# sb3.net
KiCad netlist of a schematic drawn in EAGLE
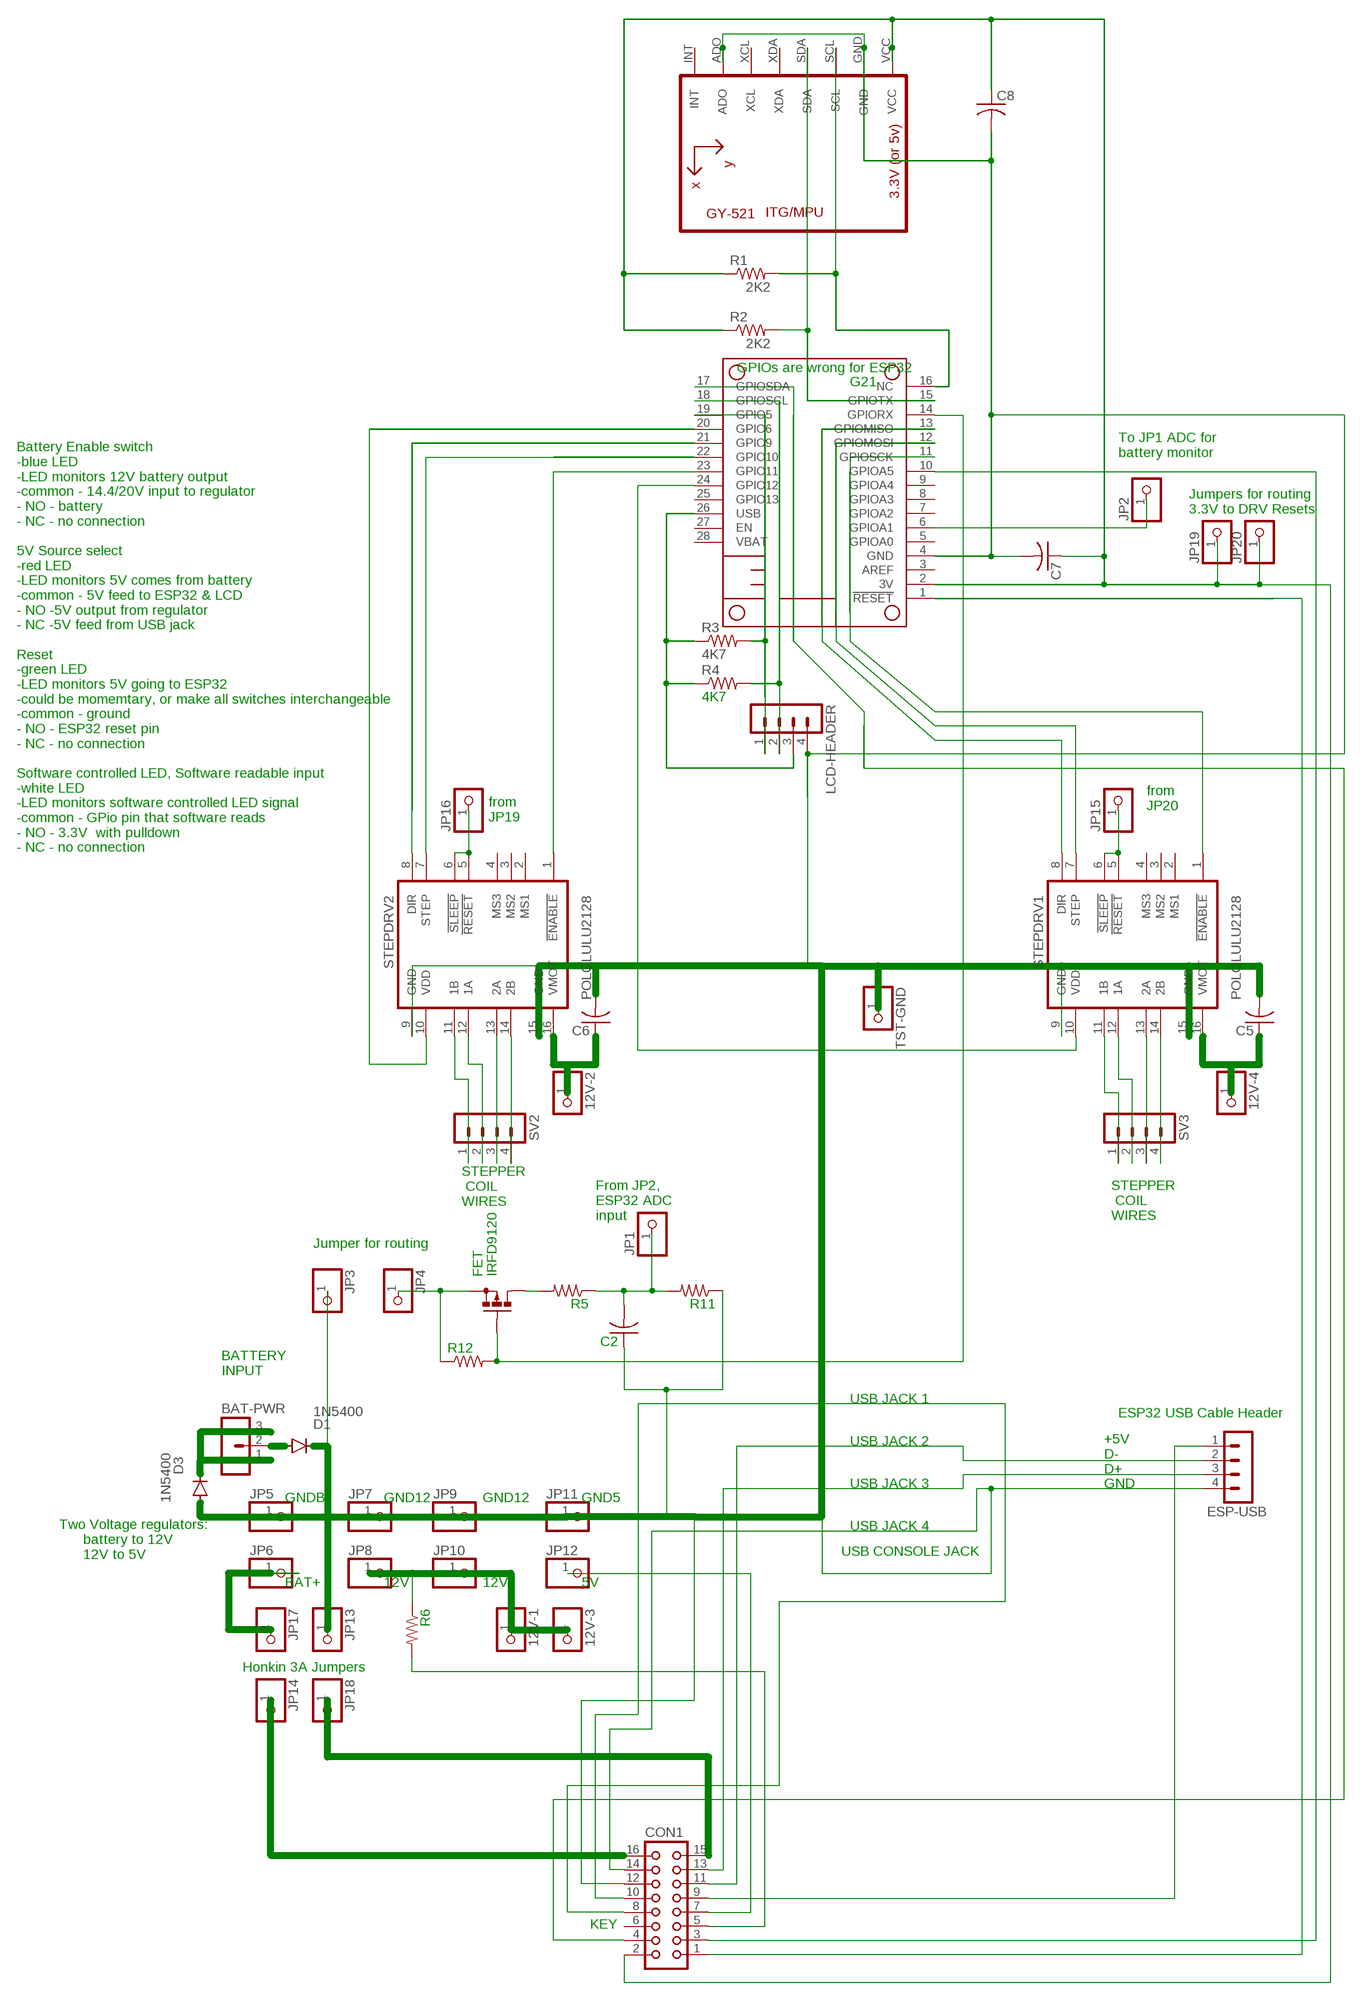
[diagram p0: schematic, sheet 1]

(export (version "E")
  (design (tool "Eeschema 10.0.6"))
  (components
    (comp (ref "12V-1")
      (value "PINHD-1X1")
      (footprint "eagle-import:1X01")
      (libsource (lib "eagle-import") (part "PINHD-1X1"))
    )
    (comp (ref "12V-2")
      (value "PINHD-1X1")
      (footprint "eagle-import:1X01")
      (libsource (lib "eagle-import") (part "PINHD-1X1"))
    )
    (comp (ref "12V-3")
      (value "PINHD-1X1")
      (footprint "eagle-import:1X01")
      (libsource (lib "eagle-import") (part "PINHD-1X1"))
    )
    (comp (ref "12V-4")
      (value "PINHD-1X1")
      (footprint "eagle-import:1X01")
      (libsource (lib "eagle-import") (part "PINHD-1X1"))
    )
    (comp (ref "BAT-PWR")
      (value "MA03-1")
      (footprint "eagle-import:MA03-1")
      (libsource (lib "eagle-import") (part "MA03-1"))
    )
    (comp (ref "C2")
      (value "C-US050-025X075")
      (footprint "eagle-import:C050-025X075")
      (libsource (lib "eagle-import") (part "C-US050-025X075"))
    )
    (comp (ref "C5")
      (value "C-US050-024X044")
      (footprint "eagle-import:C050-024X044")
      (libsource (lib "eagle-import") (part "C-US050-024X044"))
    )
    (comp (ref "C6")
      (value "C-US050-024X044")
      (footprint "eagle-import:C050-024X044")
      (libsource (lib "eagle-import") (part "C-US050-024X044"))
    )
    (comp (ref "C7")
      (value "C-US050-024X044")
      (footprint "eagle-import:C050-024X044")
      (libsource (lib "eagle-import") (part "C-US050-024X044"))
    )
    (comp (ref "C8")
      (value "C-US050-024X044")
      (footprint "eagle-import:C050-024X044")
      (libsource (lib "eagle-import") (part "C-US050-024X044"))
    )
    (comp (ref "CON1")
      (value "CON16")
      (footprint "eagle-import:CON16")
      (libsource (lib "eagle-import") (part "CON16"))
    )
    (comp (ref "D1")
      (value "1N5400")
      (footprint "eagle-import:DO201-15")
      (libsource (lib "eagle-import") (part "1N5400"))
    )
    (comp (ref "D3")
      (value "1N5400")
      (footprint "eagle-import:DO201-15")
      (libsource (lib "eagle-import") (part "1N5400"))
    )
    (comp (ref "ESP-USB")
      (value "MA04-1")
      (footprint "eagle-import:MA04-1")
      (libsource (lib "eagle-import") (part "MA04-1"))
    )
    (comp (ref "FET")
      (value "IRFD9120")
      (footprint "eagle-import:C370-01")
      (libsource (lib "eagle-import") (part "IRFD9120"))
    )
    (comp (ref "JP1")
      (value "PINHD-1X1")
      (footprint "eagle-import:1X01")
      (libsource (lib "eagle-import") (part "PINHD-1X1"))
    )
    (comp (ref "JP2")
      (value "PINHD-1X1")
      (footprint "eagle-import:1X01")
      (libsource (lib "eagle-import") (part "PINHD-1X1"))
    )
    (comp (ref "JP3")
      (value "PINHD-1X1")
      (footprint "eagle-import:1X01")
      (libsource (lib "eagle-import") (part "PINHD-1X1"))
    )
    (comp (ref "JP4")
      (value "PINHD-1X1")
      (footprint "eagle-import:1X01")
      (libsource (lib "eagle-import") (part "PINHD-1X1"))
    )
    (comp (ref "JP5")
      (value "PINHD-1X1")
      (footprint "eagle-import:1X01")
      (libsource (lib "eagle-import") (part "PINHD-1X1"))
    )
    (comp (ref "JP6")
      (value "PINHD-1X1")
      (footprint "eagle-import:1X01")
      (libsource (lib "eagle-import") (part "PINHD-1X1"))
    )
    (comp (ref "JP7")
      (value "PINHD-1X1")
      (footprint "eagle-import:1X01")
      (libsource (lib "eagle-import") (part "PINHD-1X1"))
    )
    (comp (ref "JP8")
      (value "PINHD-1X1")
      (footprint "eagle-import:1X01")
      (libsource (lib "eagle-import") (part "PINHD-1X1"))
    )
    (comp (ref "JP9")
      (value "PINHD-1X1")
      (footprint "eagle-import:1X01")
      (libsource (lib "eagle-import") (part "PINHD-1X1"))
    )
    (comp (ref "JP10")
      (value "PINHD-1X1")
      (footprint "eagle-import:1X01")
      (libsource (lib "eagle-import") (part "PINHD-1X1"))
    )
    (comp (ref "JP11")
      (value "PINHD-1X1")
      (footprint "eagle-import:1X01")
      (libsource (lib "eagle-import") (part "PINHD-1X1"))
    )
    (comp (ref "JP12")
      (value "PINHD-1X1")
      (footprint "eagle-import:1X01")
      (libsource (lib "eagle-import") (part "PINHD-1X1"))
    )
    (comp (ref "JP13")
      (value "PINHD-1X1")
      (footprint "eagle-import:1X01")
      (libsource (lib "eagle-import") (part "PINHD-1X1"))
    )
    (comp (ref "JP14")
      (value "PINHD-1X1")
      (footprint "eagle-import:1X01")
      (libsource (lib "eagle-import") (part "PINHD-1X1"))
    )
    (comp (ref "JP15")
      (value "PINHD-1X1")
      (footprint "eagle-import:1X01")
      (libsource (lib "eagle-import") (part "PINHD-1X1"))
    )
    (comp (ref "JP16")
      (value "PINHD-1X1")
      (footprint "eagle-import:1X01")
      (libsource (lib "eagle-import") (part "PINHD-1X1"))
    )
    (comp (ref "JP17")
      (value "PINHD-1X1")
      (footprint "eagle-import:1X01")
      (libsource (lib "eagle-import") (part "PINHD-1X1"))
    )
    (comp (ref "JP18")
      (value "PINHD-1X1")
      (footprint "eagle-import:1X01")
      (libsource (lib "eagle-import") (part "PINHD-1X1"))
    )
    (comp (ref "JP19")
      (value "PINHD-1X1")
      (footprint "eagle-import:1X01")
      (libsource (lib "eagle-import") (part "PINHD-1X1"))
    )
    (comp (ref "JP20")
      (value "PINHD-1X1")
      (footprint "eagle-import:1X01")
      (libsource (lib "eagle-import") (part "PINHD-1X1"))
    )
    (comp (ref "LCD-HEADER")
      (value "MA04-1")
      (footprint "eagle-import:MA04-1")
      (libsource (lib "eagle-import") (part "MA04-1"))
    )
    (comp (ref "MS2")
      (value "FEATHERWING_NOHOLES")
      (footprint "eagle-import:FEATHERWING_NOHOLES")
      (libsource (lib "eagle-import") (part "FEATHERWING_NOHOLES"))
    )
    (comp (ref "R1")
      (value "2K2")
      (footprint "eagle-import:0309_12")
      (libsource (lib "eagle-import") (part "resistor_348_R-US_0309/12"))
    )
    (comp (ref "R2")
      (value "2K2")
      (footprint "eagle-import:0309_12")
      (libsource (lib "eagle-import") (part "resistor_348_R-US_0309/12"))
    )
    (comp (ref "R3")
      (value "4K7")
      (footprint "eagle-import:0309_12")
      (libsource (lib "eagle-import") (part "resistor_348_R-US_0309/12"))
    )
    (comp (ref "R4")
      (value "4K7")
      (footprint "eagle-import:0309_12")
      (libsource (lib "eagle-import") (part "resistor_348_R-US_0309/12"))
    )
    (comp (ref "R5")
      (value "R-US_0207/10")
      (footprint "eagle-import:0207_10")
      (libsource (lib "eagle-import") (part "R-US_0207/10"))
    )
    (comp (ref "R6")
      (value "R-US_0207/10")
      (footprint "eagle-import:0207_10")
      (libsource (lib "eagle-import") (part "R-US_0207/10"))
    )
    (comp (ref "R11")
      (value "R-US_0207/10")
      (footprint "eagle-import:0207_10")
      (libsource (lib "eagle-import") (part "R-US_0207/10"))
    )
    (comp (ref "R12")
      (value "R-US_0207/10")
      (footprint "eagle-import:0207_10")
      (libsource (lib "eagle-import") (part "R-US_0207/10"))
    )
    (comp (ref "STEPDRV1")
      (value "POLOLULU2128")
      (footprint "eagle-import:POLOLULU2128")
      (libsource (lib "eagle-import") (part "POLOLULU2128"))
    )
    (comp (ref "STEPDRV2")
      (value "POLOLULU2128")
      (footprint "eagle-import:POLOLULU2128")
      (libsource (lib "eagle-import") (part "POLOLULU2128"))
    )
    (comp (ref "SV2")
      (value "MA04-1")
      (footprint "eagle-import:MA04-1")
      (libsource (lib "eagle-import") (part "MA04-1"))
    )
    (comp (ref "SV3")
      (value "MA04-1")
      (footprint "eagle-import:MA04-1")
      (libsource (lib "eagle-import") (part "MA04-1"))
    )
    (comp (ref "TST-GND")
      (value "PINHD-1X1")
      (footprint "eagle-import:1X01")
      (libsource (lib "eagle-import") (part "PINHD-1X1"))
    )
    (comp (ref "U1")
      (value "GY-521MPU6050")
      (footprint "eagle-import:GY-521")
      (libsource (lib "eagle-import") (part "GY-521MPU6050"))
    )
  )
  (nets
    (net (code "1") (name "/VBAT") (class "Default")
      (node (ref "MS2") (pin "28") (pinfunction "VBAT_28") (pintype "power_in"))
    )
    (net (code "2") (name "Net-(12V-1-Pad1)") (class "Default")
      (node (ref "12V-1") (pin "1") (pinfunction "1_1") (pintype "passive"))
      (node (ref "12V-3") (pin "1") (pinfunction "1_1") (pintype "passive"))
      (node (ref "JP10") (pin "1") (pinfunction "1_1") (pintype "passive"))
      (node (ref "JP8") (pin "1") (pinfunction "1_1") (pintype "passive"))
      (node (ref "R6") (pin "1") (pinfunction "1_1") (pintype "passive"))
    )
    (net (code "3") (name "Net-(BAT-PWR-Pad1)") (class "Default")
      (node (ref "BAT-PWR") (pin "1") (pinfunction "1_1") (pintype "passive"))
      (node (ref "BAT-PWR") (pin "3") (pinfunction "3_3") (pintype "passive"))
      (node (ref "D3") (pin "C") (pinfunction "C_C") (pintype "passive"))
    )
    (net (code "4") (name "Net-(BAT-PWR-Pad2)") (class "Default")
      (node (ref "BAT-PWR") (pin "2") (pinfunction "2_2") (pintype "passive"))
      (node (ref "D1") (pin "A") (pinfunction "A_A") (pintype "passive"))
    )
    (net (code "5") (name "Net-(C2-Pad2)") (class "Default")
      (node (ref "C2") (pin "2") (pinfunction "2_2") (pintype "passive"))
      (node (ref "JP1") (pin "1") (pinfunction "1_1") (pintype "passive"))
      (node (ref "R11") (pin "2") (pinfunction "2_2") (pintype "passive"))
      (node (ref "R5") (pin "1") (pinfunction "1_1") (pintype "passive"))
    )
    (net (code "6") (name "Net-(CON1-Pad5)") (class "Default")
      (node (ref "CON1") (pin "5") (pinfunction "5_5") (pintype "passive"))
      (node (ref "R6") (pin "2") (pinfunction "2_2") (pintype "passive"))
    )
    (net (code "7") (name "Net-(CON1-Pad7)") (class "Default")
      (node (ref "CON1") (pin "7") (pinfunction "7_7") (pintype "passive"))
      (node (ref "JP12") (pin "1") (pinfunction "1_1") (pintype "passive"))
    )
    (net (code "8") (name "Net-(CON1-Pad9)") (class "Default")
      (node (ref "CON1") (pin "9") (pinfunction "9_9") (pintype "passive"))
      (node (ref "ESP-USB") (pin "1") (pinfunction "1_1") (pintype "passive"))
    )
    (net (code "9") (name "Net-(CON1-Pad10)") (class "Default")
      (node (ref "CON1") (pin "10") (pinfunction "10_10") (pintype "passive"))
      (node (ref "CON1") (pin "8") (pinfunction "8_8") (pintype "passive"))
    )
    (net (code "10") (name "Net-(CON1-Pad11)") (class "Default")
      (node (ref "CON1") (pin "11") (pinfunction "11_11") (pintype "passive"))
      (node (ref "ESP-USB") (pin "2") (pinfunction "2_2") (pintype "passive"))
    )
    (net (code "11") (name "Net-(CON1-Pad13)") (class "Default")
      (node (ref "CON1") (pin "13") (pinfunction "13_13") (pintype "passive"))
      (node (ref "ESP-USB") (pin "3") (pinfunction "3_3") (pintype "passive"))
    )
    (net (code "12") (name "Net-(CON1-Pad15)") (class "Default")
      (node (ref "CON1") (pin "15") (pinfunction "15_15") (pintype "passive"))
      (node (ref "JP18") (pin "1") (pinfunction "1_1") (pintype "passive"))
    )
    (net (code "13") (name "Net-(CON1-Pad16)") (class "Default")
      (node (ref "CON1") (pin "16") (pinfunction "16_16") (pintype "passive"))
      (node (ref "JP14") (pin "1") (pinfunction "1_1") (pintype "passive"))
    )
    (net (code "14") (name "Net-(D1-PadC)") (class "Default")
      (node (ref "D1") (pin "C") (pinfunction "C_C") (pintype "passive"))
      (node (ref "JP13") (pin "1") (pinfunction "1_1") (pintype "passive"))
      (node (ref "JP3") (pin "1") (pinfunction "1_1") (pintype "passive"))
    )
    (net (code "15") (name "Net-(FET-D-PadD1)") (class "Default")
      (node (ref "FET") (pin "D") (pinfunction "D_D") (pintype "passive"))
      (node (ref "FET") (pin "D1") (pinfunction "D_D1") (pintype "passive"))
      (node (ref "R5") (pin "2") (pinfunction "2_2") (pintype "passive"))
    )
    (net (code "16") (name "Net-(FET-PadS)") (class "Default")
      (node (ref "FET") (pin "S") (pinfunction "S_S") (pintype "passive"))
      (node (ref "JP4") (pin "1") (pinfunction "1_1") (pintype "passive"))
      (node (ref "R12") (pin "1") (pinfunction "1_1") (pintype "passive"))
    )
    (net (code "17") (name "Net-(JP17-Pad1)") (class "Default")
      (node (ref "JP17") (pin "1") (pinfunction "1_1") (pintype "passive"))
      (node (ref "JP6") (pin "1") (pinfunction "1_1") (pintype "passive"))
    )
    (net (code "18") (name "Net-(MS2-3V)") (class "Default")
      (node (ref "C7") (pin "1") (pinfunction "1_1") (pintype "passive"))
      (node (ref "C8") (pin "1") (pinfunction "1_1") (pintype "passive"))
      (node (ref "CON1") (pin "2") (pinfunction "2_2") (pintype "passive"))
      (node (ref "JP19") (pin "1") (pinfunction "1_1") (pintype "passive"))
      (node (ref "JP20") (pin "1") (pinfunction "1_1") (pintype "passive"))
      (node (ref "MS2") (pin "2") (pinfunction "3V_2") (pintype "power_in"))
      (node (ref "R1") (pin "1") (pinfunction "1_1") (pintype "passive"))
      (node (ref "R2") (pin "1") (pinfunction "1_1") (pintype "passive"))
      (node (ref "U1") (pin "VCC") (pinfunction "VCC_VCC") (pintype "bidirectional"))
    )
    (net (code "19") (name "Net-(MS2-GND)") (class "Default")
      (node (ref "C2") (pin "1") (pinfunction "1_1") (pintype "passive"))
      (node (ref "C5") (pin "2") (pinfunction "2_2") (pintype "passive"))
      (node (ref "C6") (pin "2") (pinfunction "2_2") (pintype "passive"))
      (node (ref "C7") (pin "2") (pinfunction "2_2") (pintype "passive"))
      (node (ref "C8") (pin "2") (pinfunction "2_2") (pintype "passive"))
      (node (ref "CON1") (pin "12") (pinfunction "12_12") (pintype "passive"))
      (node (ref "CON1") (pin "14") (pinfunction "14_14") (pintype "passive"))
      (node (ref "D3") (pin "A") (pinfunction "A_A") (pintype "passive"))
      (node (ref "ESP-USB") (pin "4") (pinfunction "4_4") (pintype "passive"))
      (node (ref "JP11") (pin "1") (pinfunction "1_1") (pintype "passive"))
      (node (ref "JP5") (pin "1") (pinfunction "1_1") (pintype "passive"))
      (node (ref "JP7") (pin "1") (pinfunction "1_1") (pintype "passive"))
      (node (ref "JP9") (pin "1") (pinfunction "1_1") (pintype "passive"))
      (node (ref "LCD-HEADER") (pin "4") (pinfunction "4_4") (pintype "passive"))
      (node (ref "MS2") (pin "4") (pinfunction "GND_4") (pintype "power_in"))
      (node (ref "R11") (pin "1") (pinfunction "1_1") (pintype "passive"))
      (node (ref "STEPDRV1") (pin "15") (pinfunction "GND_15") (pintype "power_in"))
      (node (ref "STEPDRV1") (pin "9") (pinfunction "GND_9") (pintype "power_in"))
      (node (ref "STEPDRV2") (pin "15") (pinfunction "GND_15") (pintype "power_in"))
      (node (ref "STEPDRV2") (pin "9") (pinfunction "GND_9") (pintype "power_in"))
      (node (ref "TST-GND") (pin "1") (pinfunction "1_1") (pintype "passive"))
      (node (ref "U1") (pin "ADO") (pinfunction "ADO_ADO") (pintype "bidirectional"))
      (node (ref "U1") (pin "GND") (pinfunction "GND_GND") (pintype "bidirectional"))
    )
    (net (code "20") (name "Net-(MS2-GPIO5)") (class "Default")
      (node (ref "LCD-HEADER") (pin "1") (pinfunction "1_1") (pintype "passive"))
      (node (ref "MS2") (pin "19") (pinfunction "GPIO5_19") (pintype "bidirectional"))
      (node (ref "R3") (pin "2") (pinfunction "2_2") (pintype "passive"))
    )
    (net (code "21") (name "Net-(MS2-GPIO6)") (class "Default")
      (node (ref "MS2") (pin "20") (pinfunction "GPIO6_20") (pintype "bidirectional"))
      (node (ref "STEPDRV2") (pin "10") (pinfunction "VDD_10") (pintype "power_in"))
    )
    (net (code "22") (name "Net-(MS2-GPIO9)") (class "Default")
      (node (ref "MS2") (pin "21") (pinfunction "GPIO9_21") (pintype "bidirectional"))
      (node (ref "STEPDRV2") (pin "8") (pinfunction "DIR_8") (pintype "input"))
    )
    (net (code "23") (name "Net-(MS2-GPIO10)") (class "Default")
      (node (ref "MS2") (pin "22") (pinfunction "GPIO10_22") (pintype "bidirectional"))
      (node (ref "STEPDRV2") (pin "7") (pinfunction "STEP_7") (pintype "input"))
    )
    (net (code "24") (name "Net-(MS2-GPIO11)") (class "Default")
      (node (ref "MS2") (pin "23") (pinfunction "GPIO11_23") (pintype "bidirectional"))
      (node (ref "STEPDRV2") (pin "1") (pinfunction "~{ENABLE}_1") (pintype "input"))
    )
    (net (code "25") (name "Net-(MS2-GPIO12)") (class "Default")
      (node (ref "MS2") (pin "24") (pinfunction "GPIO12_24") (pintype "bidirectional"))
      (node (ref "STEPDRV1") (pin "10") (pinfunction "VDD_10") (pintype "power_in"))
    )
    (net (code "26") (name "Net-(MS2-GPIOA1)") (class "Default")
      (node (ref "JP2") (pin "1") (pinfunction "1_1") (pintype "passive"))
      (node (ref "MS2") (pin "6") (pinfunction "GPIOA1_6") (pintype "bidirectional"))
    )
    (net (code "27") (name "Net-(MS2-GPIOA5)") (class "Default")
      (node (ref "CON1") (pin "3") (pinfunction "3_3") (pintype "passive"))
      (node (ref "MS2") (pin "10") (pinfunction "GPIOA5_10") (pintype "bidirectional"))
    )
    (net (code "28") (name "Net-(MS2-GPIOMISO)") (class "Default")
      (node (ref "MS2") (pin "13") (pinfunction "GPIOMISO_13") (pintype "bidirectional"))
      (node (ref "STEPDRV1") (pin "8") (pinfunction "DIR_8") (pintype "input"))
    )
    (net (code "29") (name "Net-(MS2-GPIOMOSI)") (class "Default")
      (node (ref "MS2") (pin "12") (pinfunction "GPIOMOSI_12") (pintype "bidirectional"))
      (node (ref "STEPDRV1") (pin "7") (pinfunction "STEP_7") (pintype "input"))
    )
    (net (code "30") (name "Net-(MS2-GPIORX)") (class "Default")
      (node (ref "FET") (pin "G") (pinfunction "G_G") (pintype "passive"))
      (node (ref "MS2") (pin "14") (pinfunction "GPIORX_14") (pintype "bidirectional"))
      (node (ref "R12") (pin "2") (pinfunction "2_2") (pintype "passive"))
    )
    (net (code "31") (name "Net-(MS2-GPIOSCK)") (class "Default")
      (node (ref "MS2") (pin "11") (pinfunction "GPIOSCK_11") (pintype "bidirectional"))
      (node (ref "STEPDRV1") (pin "1") (pinfunction "~{ENABLE}_1") (pintype "input"))
    )
    (net (code "32") (name "Net-(MS2-GPIOSCL)") (class "Default")
      (node (ref "LCD-HEADER") (pin "2") (pinfunction "2_2") (pintype "passive"))
      (node (ref "MS2") (pin "18") (pinfunction "GPIOSCL_18") (pintype "bidirectional"))
      (node (ref "R4") (pin "2") (pinfunction "2_2") (pintype "passive"))
    )
    (net (code "33") (name "Net-(MS2-GPIOSDA)") (class "Default")
      (node (ref "CON1") (pin "4") (pinfunction "4_4") (pintype "passive"))
      (node (ref "MS2") (pin "17") (pinfunction "GPIOSDA_17") (pintype "bidirectional"))
    )
    (net (code "34") (name "Net-(MS2-GPIOTX)") (class "Default")
      (node (ref "MS2") (pin "15") (pinfunction "GPIOTX_15") (pintype "bidirectional"))
      (node (ref "R2") (pin "2") (pinfunction "2_2") (pintype "passive"))
      (node (ref "U1") (pin "SDA") (pinfunction "SDA_SDA") (pintype "bidirectional"))
    )
    (net (code "35") (name "Net-(MS2-NC)") (class "Default")
      (node (ref "MS2") (pin "16") (pinfunction "NC_16") (pintype "passive"))
      (node (ref "R1") (pin "2") (pinfunction "2_2") (pintype "passive"))
      (node (ref "U1") (pin "SCL") (pinfunction "SCL_SCL") (pintype "bidirectional"))
    )
    (net (code "36") (name "Net-(MS2-USB)") (class "Default")
      (node (ref "LCD-HEADER") (pin "3") (pinfunction "3_3") (pintype "passive"))
      (node (ref "MS2") (pin "26") (pinfunction "USB_26") (pintype "power_in"))
      (node (ref "R3") (pin "1") (pinfunction "1_1") (pintype "passive"))
      (node (ref "R4") (pin "1") (pinfunction "1_1") (pintype "passive"))
    )
    (net (code "37") (name "Net-(MS2-~{RESET})") (class "Default")
      (node (ref "CON1") (pin "1") (pinfunction "1_1") (pintype "passive"))
      (node (ref "MS2") (pin "1") (pinfunction "~{RESET}_1") (pintype "input"))
    )
    (net (code "38") (name "Net-(STEPDRV1-1A)") (class "Default")
      (node (ref "STEPDRV1") (pin "12") (pinfunction "1A_12") (pintype "output"))
      (node (ref "SV3") (pin "2") (pinfunction "2_2") (pintype "passive"))
    )
    (net (code "39") (name "Net-(STEPDRV1-1B)") (class "Default")
      (node (ref "STEPDRV1") (pin "11") (pinfunction "1B_11") (pintype "output"))
      (node (ref "SV3") (pin "1") (pinfunction "1_1") (pintype "passive"))
    )
    (net (code "40") (name "Net-(STEPDRV1-2A)") (class "Default")
      (node (ref "STEPDRV1") (pin "13") (pinfunction "2A_13") (pintype "output"))
      (node (ref "SV3") (pin "3") (pinfunction "3_3") (pintype "passive"))
    )
    (net (code "41") (name "Net-(STEPDRV1-2B)") (class "Default")
      (node (ref "STEPDRV1") (pin "14") (pinfunction "2B_14") (pintype "output"))
      (node (ref "SV3") (pin "4") (pinfunction "4_4") (pintype "passive"))
    )
    (net (code "42") (name "Net-(STEPDRV1-VMOT)") (class "Default")
      (node (ref "12V-4") (pin "1") (pinfunction "1_1") (pintype "passive"))
      (node (ref "C5") (pin "1") (pinfunction "1_1") (pintype "passive"))
      (node (ref "STEPDRV1") (pin "16") (pinfunction "VMOT_16") (pintype "power_in"))
    )
    (net (code "43") (name "Net-(STEPDRV1-~{RESET})") (class "Default")
      (node (ref "JP15") (pin "1") (pinfunction "1_1") (pintype "passive"))
      (node (ref "STEPDRV1") (pin "5") (pinfunction "~{RESET}_5") (pintype "input"))
      (node (ref "STEPDRV1") (pin "6") (pinfunction "~{SLEEP}_6") (pintype "input"))
    )
    (net (code "44") (name "Net-(STEPDRV2-1A)") (class "Default")
      (node (ref "STEPDRV2") (pin "12") (pinfunction "1A_12") (pintype "output"))
      (node (ref "SV2") (pin "2") (pinfunction "2_2") (pintype "passive"))
    )
    (net (code "45") (name "Net-(STEPDRV2-1B)") (class "Default")
      (node (ref "STEPDRV2") (pin "11") (pinfunction "1B_11") (pintype "output"))
      (node (ref "SV2") (pin "1") (pinfunction "1_1") (pintype "passive"))
    )
    (net (code "46") (name "Net-(STEPDRV2-2A)") (class "Default")
      (node (ref "STEPDRV2") (pin "13") (pinfunction "2A_13") (pintype "output"))
      (node (ref "SV2") (pin "3") (pinfunction "3_3") (pintype "passive"))
    )
    (net (code "47") (name "Net-(STEPDRV2-2B)") (class "Default")
      (node (ref "STEPDRV2") (pin "14") (pinfunction "2B_14") (pintype "output"))
      (node (ref "SV2") (pin "4") (pinfunction "4_4") (pintype "passive"))
    )
    (net (code "48") (name "Net-(STEPDRV2-VMOT)") (class "Default")
      (node (ref "12V-2") (pin "1") (pinfunction "1_1") (pintype "passive"))
      (node (ref "C6") (pin "1") (pinfunction "1_1") (pintype "passive"))
      (node (ref "STEPDRV2") (pin "16") (pinfunction "VMOT_16") (pintype "power_in"))
    )
    (net (code "49") (name "Net-(STEPDRV2-~{RESET})") (class "Default")
      (node (ref "JP16") (pin "1") (pinfunction "1_1") (pintype "passive"))
      (node (ref "STEPDRV2") (pin "5") (pinfunction "~{RESET}_5") (pintype "input"))
      (node (ref "STEPDRV2") (pin "6") (pinfunction "~{SLEEP}_6") (pintype "input"))
    )
    (net (code "50") (name "unconnected-(CON1-Pad6)") (class "Default")
      (node (ref "CON1") (pin "6") (pinfunction "6_6") (pintype "passive"))
    )
    (net (code "51") (name "unconnected-(MS2-AREF-Pad3)") (class "Default")
      (node (ref "MS2") (pin "3") (pinfunction "AREF_3") (pintype "passive"))
    )
    (net (code "52") (name "unconnected-(MS2-EN-Pad27)") (class "Default")
      (node (ref "MS2") (pin "27") (pinfunction "EN_27") (pintype "passive"))
    )
    (net (code "53") (name "unconnected-(MS2-GPIO13-Pad25)") (class "Default")
      (node (ref "MS2") (pin "25") (pinfunction "GPIO13_25") (pintype "bidirectional"))
    )
    (net (code "54") (name "unconnected-(MS2-GPIOA0-Pad5)") (class "Default")
      (node (ref "MS2") (pin "5") (pinfunction "GPIOA0_5") (pintype "bidirectional"))
    )
    (net (code "55") (name "unconnected-(MS2-GPIOA2-Pad7)") (class "Default")
      (node (ref "MS2") (pin "7") (pinfunction "GPIOA2_7") (pintype "bidirectional"))
    )
    (net (code "56") (name "unconnected-(MS2-GPIOA3-Pad8)") (class "Default")
      (node (ref "MS2") (pin "8") (pinfunction "GPIOA3_8") (pintype "bidirectional"))
    )
    (net (code "57") (name "unconnected-(MS2-GPIOA4-Pad9)") (class "Default")
      (node (ref "MS2") (pin "9") (pinfunction "GPIOA4_9") (pintype "bidirectional"))
    )
    (net (code "58") (name "unconnected-(STEPDRV1-MS1-Pad2)") (class "Default")
      (node (ref "STEPDRV1") (pin "2") (pinfunction "MS1_2") (pintype "input"))
    )
    (net (code "59") (name "unconnected-(STEPDRV1-MS2-Pad3)") (class "Default")
      (node (ref "STEPDRV1") (pin "3") (pinfunction "MS2_3") (pintype "input"))
    )
    (net (code "60") (name "unconnected-(STEPDRV1-MS3-Pad4)") (class "Default")
      (node (ref "STEPDRV1") (pin "4") (pinfunction "MS3_4") (pintype "input"))
    )
    (net (code "61") (name "unconnected-(STEPDRV2-MS1-Pad2)") (class "Default")
      (node (ref "STEPDRV2") (pin "2") (pinfunction "MS1_2") (pintype "input"))
    )
    (net (code "62") (name "unconnected-(STEPDRV2-MS2-Pad3)") (class "Default")
      (node (ref "STEPDRV2") (pin "3") (pinfunction "MS2_3") (pintype "input"))
    )
    (net (code "63") (name "unconnected-(STEPDRV2-MS3-Pad4)") (class "Default")
      (node (ref "STEPDRV2") (pin "4") (pinfunction "MS3_4") (pintype "input"))
    )
    (net (code "64") (name "unconnected-(U1-PadINT)") (class "Default")
      (node (ref "U1") (pin "INT") (pinfunction "INT_INT") (pintype "bidirectional"))
    )
    (net (code "65") (name "unconnected-(U1-PadXCL)") (class "Default")
      (node (ref "U1") (pin "XCL") (pinfunction "XCL_XCL") (pintype "bidirectional"))
    )
    (net (code "66") (name "unconnected-(U1-PadXDA)") (class "Default")
      (node (ref "U1") (pin "XDA") (pinfunction "XDA_XDA") (pintype "bidirectional"))
    )
  )
)
